# ElectroII_UPDATE.net
KiCad netlist of a schematic drawn in EAGLE
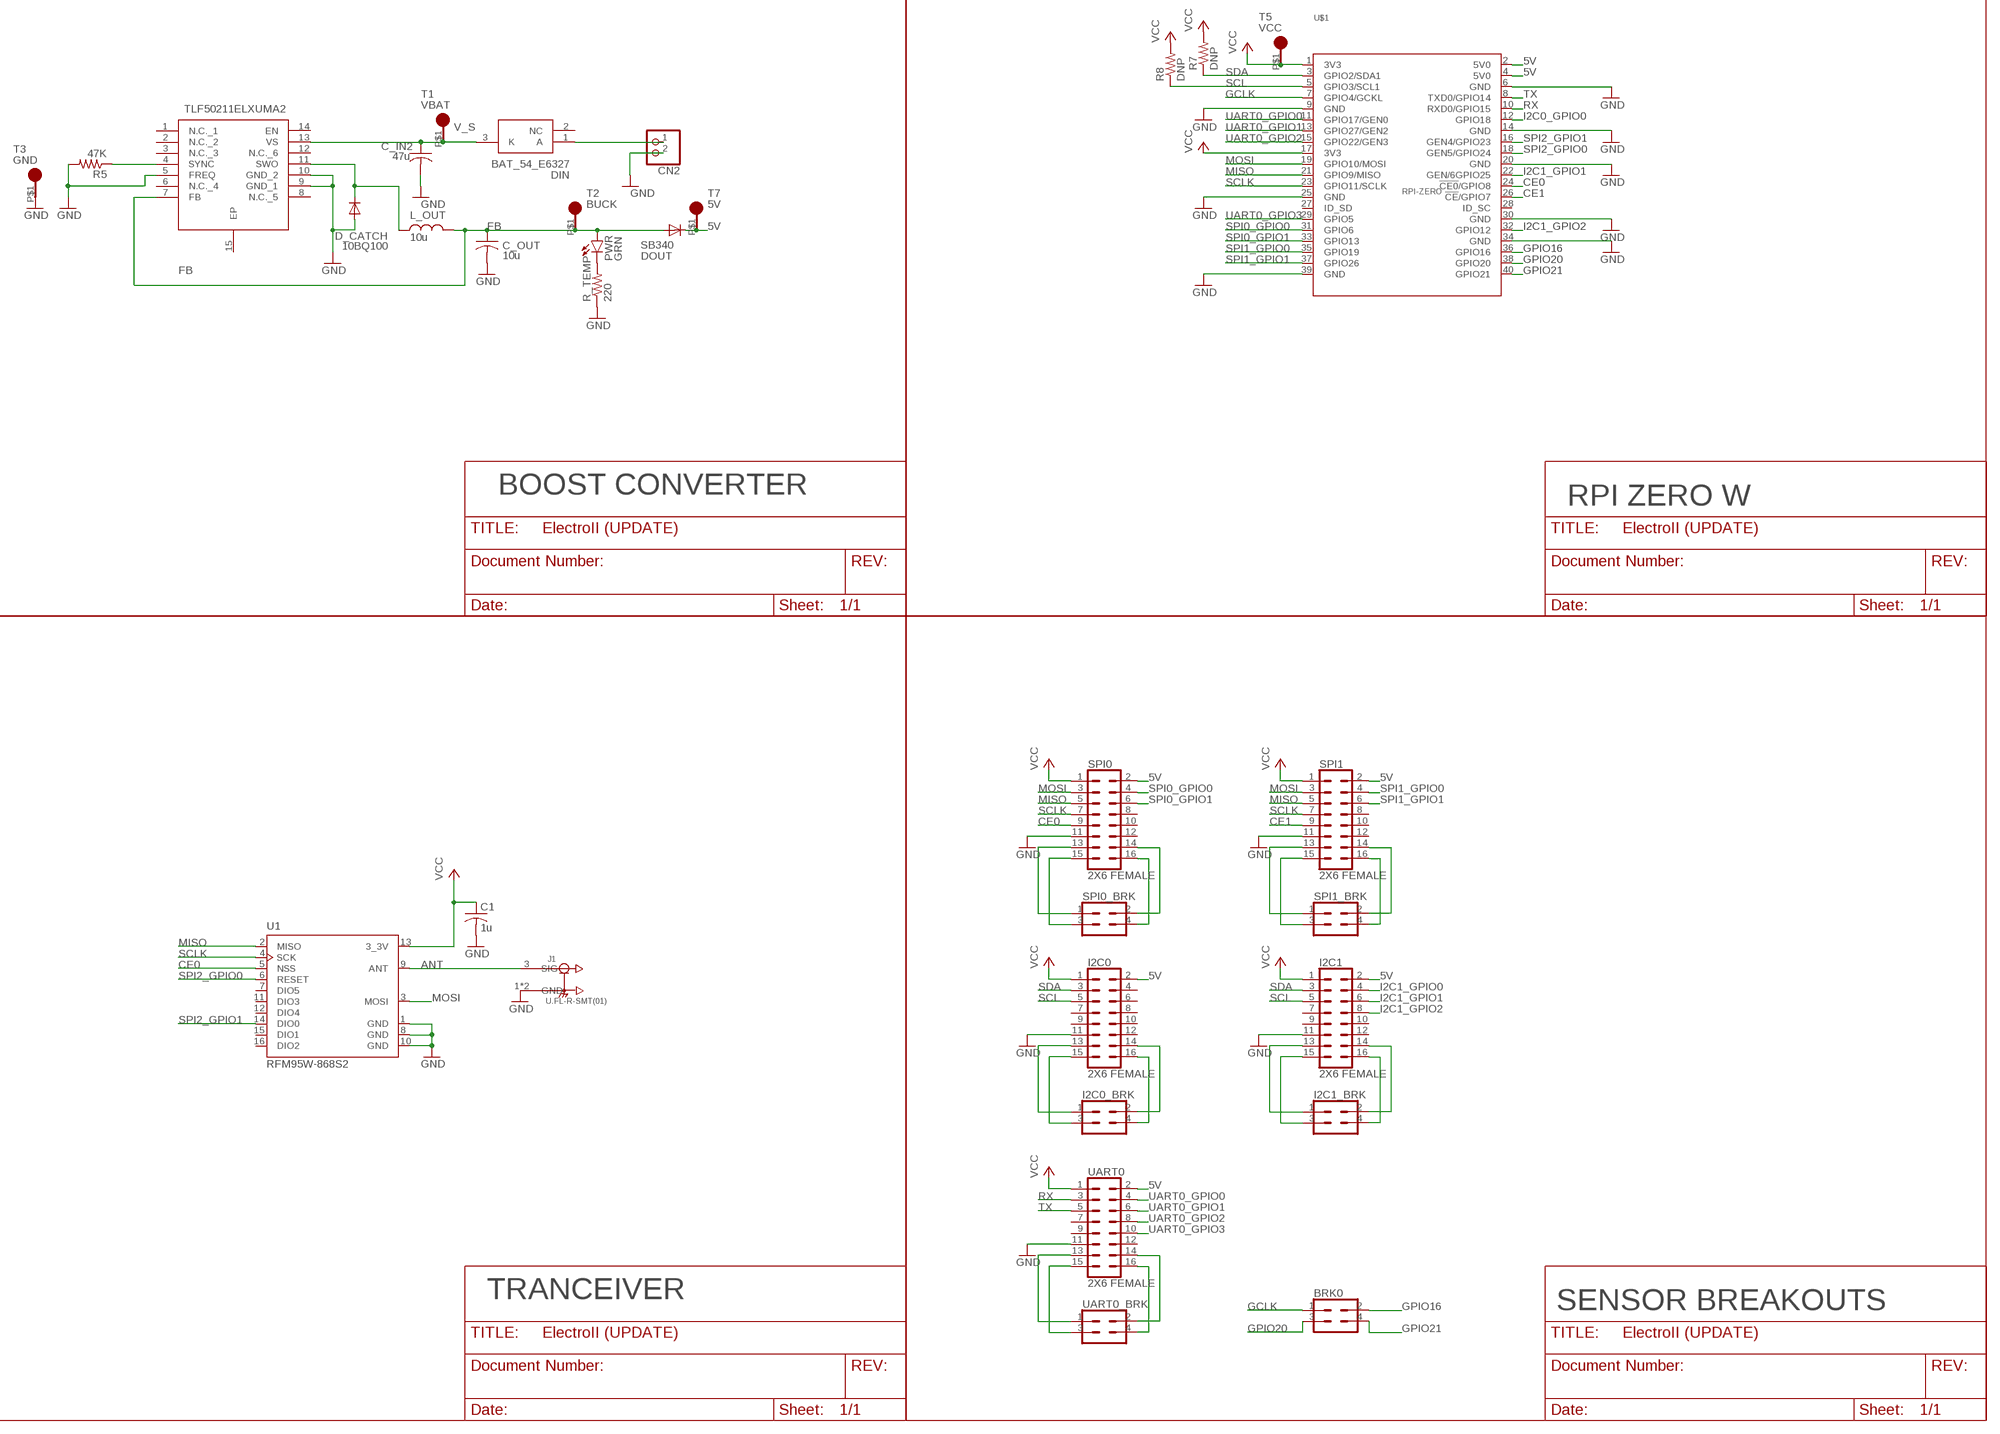
[diagram p0: schematic, sheet 1]

(export (version "E")
  (design (tool "Eeschema 10.0.6"))
  (components
    (comp (ref "BRK0")
      (value "SENSOR_PIN_BREAKOUT")
      (footprint "eagle-import:2X2")
      (libsource (lib "eagle-import") (part "SENSOR_PIN_BREAKOUT"))
    )
    (comp (ref "C1")
      (value "1u")
      (footprint "eagle-import:C1206")
      (libsource (lib "eagle-import") (part "C-ALL_PACKAGESC1206"))
    )
    (comp (ref "CN2")
      (value "JST_2PIN-SMT-RA")
      (footprint "eagle-import:JST-PH-2-SMT-RA")
      (libsource (lib "eagle-import") (part "JST_2PIN-SMT-RA"))
    )
    (comp (ref "C_IN2")
      (value "47u")
      (footprint "eagle-import:C1206")
      (libsource (lib "eagle-import") (part "C-ALL_PACKAGESC1206"))
    )
    (comp (ref "C_OUT")
      (value "10u")
      (footprint "eagle-import:C1206")
      (libsource (lib "eagle-import") (part "C-ALL_PACKAGESC1206"))
    )
    (comp (ref "DIN")
      (value "BAT_54_E6327")
      (footprint "eagle-import:SOT95P240X110-3N")
      (fields
        (field (name "MANUFACTURER_PART_NUMBER") "BAT 54 E6327")
        (field (name "MOUSER_PART_NUMBER") "726-BAT54E6327")
      )
      (libsource (lib "eagle-import") (part "BAT_54_E6327"))
    )
    (comp (ref "DOUT")
      (value "SB340")
      (footprint "eagle-import:DO41-10")
      (libsource (lib "eagle-import") (part "1N4004"))
    )
    (comp (ref "D_CATCH")
      (value "10BQ100")
      (footprint "eagle-import:DO41-10")
      (libsource (lib "eagle-import") (part "1N4004"))
    )
    (comp (ref "I2C0")
      (value "2X6 FEMALE")
      (footprint "eagle-import:2X7")
      (libsource (lib "eagle-import") (part "SENSOR_BREAKOUTPTH_FEMALE"))
    )
    (comp (ref "I2C0_BRK")
      (value "SENSOR_PIN_BREAKOUT")
      (footprint "eagle-import:2X2")
      (libsource (lib "eagle-import") (part "SENSOR_PIN_BREAKOUT"))
    )
    (comp (ref "I2C1")
      (value "2X6 FEMALE")
      (footprint "eagle-import:2X7")
      (libsource (lib "eagle-import") (part "SENSOR_BREAKOUTPTH_FEMALE"))
    )
    (comp (ref "I2C1_BRK")
      (value "SENSOR_PIN_BREAKOUT")
      (footprint "eagle-import:2X2")
      (libsource (lib "eagle-import") (part "SENSOR_PIN_BREAKOUT"))
    )
    (comp (ref "IC1")
      (value "TLF50211ELXUMA2")
      (footprint "eagle-import:SOP65P600X170-15N")
      (fields (field (name "MOUSER_PART_NUMBER") "726-TLF50211ELXUMA2"))
      (libsource (lib "eagle-import") (part "TLF50211ELXUMA2"))
    )
    (comp (ref "J1")
      (value "U.FL-R-SMT(01)")
      (footprint "eagle-import:HRS_U.FL-R-SMT(01)")
      (fields
        (field (name "DIGI-KEY_PART_NUMBER") "H9161-ND")
        (field (name "MF") "Hirose")
        (field (name "MP") "U.FL-R-SMT_01_")
      )
      (libsource (lib "eagle-import") (part "U.FL-R-SMT(01)"))
    )
    (comp (ref "L_OUT")
      (value "10u")
      (footprint "eagle-import:L-DS75LC")
      (libsource (lib "eagle-import") (part "L_SMD"))
    )
    (comp (ref "PWR")
      (value "GRN")
      (footprint "eagle-import:LED5MM")
      (libsource (lib "eagle-import") (part "LED5MM"))
    )
    (comp (ref "R5")
      (value "47K")
      (footprint "eagle-import:R1206")
      (libsource (lib "eagle-import") (part "R-ALL_PACKAGESR1206"))
    )
    (comp (ref "R7")
      (value "DNP")
      (footprint "eagle-import:R1206")
      (libsource (lib "eagle-import") (part "R-ALL_PACKAGESR1206"))
    )
    (comp (ref "R8")
      (value "DNP")
      (footprint "eagle-import:R1206")
      (libsource (lib "eagle-import") (part "R-ALL_PACKAGESR1206"))
    )
    (comp (ref "R_TEMP")
      (value "220")
      (footprint "eagle-import:R1206")
      (libsource (lib "eagle-import") (part "R-ALL_PACKAGESR1206"))
    )
    (comp (ref "SPI0")
      (value "2X6 FEMALE")
      (footprint "eagle-import:2X7")
      (libsource (lib "eagle-import") (part "SENSOR_BREAKOUTPTH_FEMALE"))
    )
    (comp (ref "SPI0_BRK")
      (value "SENSOR_PIN_BREAKOUT")
      (footprint "eagle-import:2X2")
      (libsource (lib "eagle-import") (part "SENSOR_PIN_BREAKOUT"))
    )
    (comp (ref "SPI1")
      (value "2X6 FEMALE")
      (footprint "eagle-import:2X7")
      (libsource (lib "eagle-import") (part "SENSOR_BREAKOUTPTH_FEMALE"))
    )
    (comp (ref "SPI1_BRK")
      (value "SENSOR_PIN_BREAKOUT")
      (footprint "eagle-import:2X2")
      (libsource (lib "eagle-import") (part "SENSOR_PIN_BREAKOUT"))
    )
    (comp (ref "T1")
      (value "VBAT")
      (footprint "eagle-import:TEST_PAD")
      (libsource (lib "eagle-import") (part "TEST_PAD"))
    )
    (comp (ref "T2")
      (value "BUCK")
      (footprint "eagle-import:TEST_PAD")
      (libsource (lib "eagle-import") (part "TEST_PAD"))
    )
    (comp (ref "T3")
      (value "GND")
      (footprint "eagle-import:TEST_PAD")
      (libsource (lib "eagle-import") (part "TEST_PAD"))
    )
    (comp (ref "T5")
      (value "VCC")
      (footprint "eagle-import:TEST_PAD")
      (libsource (lib "eagle-import") (part "TEST_PAD"))
    )
    (comp (ref "T7")
      (value "5V")
      (footprint "eagle-import:TEST_PAD")
      (libsource (lib "eagle-import") (part "TEST_PAD"))
    )
    (comp (ref "U$1")
      (value "RPI-ZERO")
      (footprint "eagle-import:RASP_PI_ZERO_BOARD_FULL")
      (libsource (lib "eagle-import") (part "RPI-ZERO"))
    )
    (comp (ref "U1")
      (value "RFM95W-868S2")
      (footprint "eagle-import:XCVR_RFM95W-868S2")
      (fields (field (name "MF") "RF"))
      (libsource (lib "eagle-import") (part "RFM95W-868S2"))
    )
    (comp (ref "UART0")
      (value "2X6 FEMALE")
      (footprint "eagle-import:2X7")
      (libsource (lib "eagle-import") (part "SENSOR_BREAKOUTPTH_FEMALE"))
    )
    (comp (ref "UART0_BRK")
      (value "SENSOR_PIN_BREAKOUT")
      (footprint "eagle-import:2X2")
      (libsource (lib "eagle-import") (part "SENSOR_PIN_BREAKOUT"))
    )
  )
  (nets
    (net (code "1") (name "/5V") (class "Default")
      (node (ref "DOUT") (pin "C") (pinfunction "C_C") (pintype "passive"))
      (node (ref "I2C0") (pin "2") (pinfunction "2_2") (pintype "passive"))
      (node (ref "I2C1") (pin "2") (pinfunction "2_2") (pintype "passive"))
      (node (ref "SPI0") (pin "2") (pinfunction "2_2") (pintype "passive"))
      (node (ref "SPI1") (pin "2") (pinfunction "2_2") (pintype "passive"))
      (node (ref "T7") (pin "P$1") (pinfunction "P$1_P$1") (pintype "passive"))
      (node (ref "U$1") (pin "2") (pinfunction "5V0_2") (pintype "power_in"))
      (node (ref "U$1") (pin "4") (pinfunction "5V0_4") (pintype "power_in"))
      (node (ref "UART0") (pin "2") (pinfunction "2_2") (pintype "passive"))
    )
    (net (code "2") (name "/ANT") (class "Default")
      (node (ref "J1") (pin "3") (pinfunction "SIG_3") (pintype "passive"))
      (node (ref "U1") (pin "9") (pinfunction "ANT_9") (pintype "passive"))
    )
    (net (code "3") (name "/CE0") (class "Default")
      (node (ref "SPI0") (pin "9") (pinfunction "9_9") (pintype "passive"))
      (node (ref "U$1") (pin "24") (pinfunction "~{CE0}/GPIO8_24") (pintype "bidirectional"))
      (node (ref "U1") (pin "5") (pinfunction "NSS_5") (pintype "input"))
    )
    (net (code "4") (name "/CE1") (class "Default")
      (node (ref "SPI1") (pin "9") (pinfunction "9_9") (pintype "passive"))
      (node (ref "U$1") (pin "26") (pinfunction "~{CE}/GPIO7_26") (pintype "bidirectional"))
    )
    (net (code "5") (name "/FB") (class "Default")
      (node (ref "C_OUT") (pin "1") (pinfunction "1_1") (pintype "passive"))
      (node (ref "DOUT") (pin "A") (pinfunction "A_A") (pintype "passive"))
      (node (ref "IC1") (pin "7") (pinfunction "FB_7") (pintype "bidirectional"))
      (node (ref "L_OUT") (pin "P$2") (pinfunction "2_P$2") (pintype "passive"))
      (node (ref "PWR") (pin "A") (pinfunction "A_A") (pintype "passive"))
      (node (ref "T2") (pin "P$1") (pinfunction "P$1_P$1") (pintype "passive"))
    )
    (net (code "6") (name "/GCLK") (class "Default")
      (node (ref "BRK0") (pin "1") (pinfunction "1_1") (pintype "passive"))
      (node (ref "U$1") (pin "7") (pinfunction "GPIO4/GCKL_7") (pintype "bidirectional"))
    )
    (net (code "7") (name "/GPIO16") (class "Default")
      (node (ref "BRK0") (pin "2") (pinfunction "2_2") (pintype "passive"))
      (node (ref "U$1") (pin "36") (pinfunction "GPIO16_36") (pintype "bidirectional"))
    )
    (net (code "8") (name "/GPIO20") (class "Default")
      (node (ref "BRK0") (pin "3") (pinfunction "3_3") (pintype "passive"))
      (node (ref "U$1") (pin "38") (pinfunction "GPIO20_38") (pintype "bidirectional"))
    )
    (net (code "9") (name "/GPIO21") (class "Default")
      (node (ref "BRK0") (pin "4") (pinfunction "4_4") (pintype "passive"))
      (node (ref "U$1") (pin "40") (pinfunction "GPIO21_40") (pintype "bidirectional"))
    )
    (net (code "10") (name "/I2C0_GPIO0") (class "Default")
      (node (ref "U$1") (pin "12") (pinfunction "GPIO18_12") (pintype "bidirectional"))
    )
    (net (code "11") (name "/I2C1_GPIO0") (class "Default")
      (node (ref "I2C1") (pin "4") (pinfunction "4_4") (pintype "passive"))
    )
    (net (code "12") (name "/I2C1_GPIO1") (class "Default")
      (node (ref "I2C1") (pin "6") (pinfunction "6_6") (pintype "passive"))
      (node (ref "U$1") (pin "22") (pinfunction "GEN/6GPIO25_22") (pintype "bidirectional"))
    )
    (net (code "13") (name "/I2C1_GPIO2") (class "Default")
      (node (ref "I2C1") (pin "8") (pinfunction "8_8") (pintype "passive"))
      (node (ref "U$1") (pin "32") (pinfunction "GPIO12_32") (pintype "bidirectional"))
    )
    (net (code "14") (name "/MISO") (class "Default")
      (node (ref "SPI0") (pin "5") (pinfunction "5_5") (pintype "passive"))
      (node (ref "SPI1") (pin "5") (pinfunction "5_5") (pintype "passive"))
      (node (ref "U$1") (pin "21") (pinfunction "GPIO9/MISO_21") (pintype "bidirectional"))
      (node (ref "U1") (pin "2") (pinfunction "MISO_2") (pintype "input"))
    )
    (net (code "15") (name "/MOSI") (class "Default")
      (node (ref "SPI0") (pin "3") (pinfunction "3_3") (pintype "passive"))
      (node (ref "SPI1") (pin "3") (pinfunction "3_3") (pintype "passive"))
      (node (ref "U$1") (pin "19") (pinfunction "GPIO10/MOSI_19") (pintype "bidirectional"))
      (node (ref "U1") (pin "3") (pinfunction "MOSI_3") (pintype "output"))
    )
    (net (code "16") (name "/RX") (class "Default")
      (node (ref "U$1") (pin "10") (pinfunction "RXD0/GPIO15_10") (pintype "bidirectional"))
      (node (ref "UART0") (pin "3") (pinfunction "3_3") (pintype "passive"))
    )
    (net (code "17") (name "/SCL") (class "Default")
      (node (ref "I2C0") (pin "5") (pinfunction "5_5") (pintype "passive"))
      (node (ref "I2C1") (pin "5") (pinfunction "5_5") (pintype "passive"))
      (node (ref "R8") (pin "1") (pinfunction "1_1") (pintype "passive"))
      (node (ref "U$1") (pin "5") (pinfunction "GPIO3/SCL1_5") (pintype "bidirectional"))
    )
    (net (code "18") (name "/SCLK") (class "Default")
      (node (ref "SPI0") (pin "7") (pinfunction "7_7") (pintype "passive"))
      (node (ref "SPI1") (pin "7") (pinfunction "7_7") (pintype "passive"))
      (node (ref "U$1") (pin "23") (pinfunction "GPIO11/SCLK_23") (pintype "bidirectional"))
      (node (ref "U1") (pin "4") (pinfunction "SCK_4") (pintype "input"))
    )
    (net (code "19") (name "/SDA") (class "Default")
      (node (ref "I2C0") (pin "3") (pinfunction "3_3") (pintype "passive"))
      (node (ref "I2C1") (pin "3") (pinfunction "3_3") (pintype "passive"))
      (node (ref "R7") (pin "1") (pinfunction "1_1") (pintype "passive"))
      (node (ref "U$1") (pin "3") (pinfunction "GPIO2/SDA1_3") (pintype "bidirectional"))
    )
    (net (code "20") (name "/SPI0_GPIO0") (class "Default")
      (node (ref "SPI0") (pin "4") (pinfunction "4_4") (pintype "passive"))
      (node (ref "U$1") (pin "31") (pinfunction "GPIO6_31") (pintype "bidirectional"))
    )
    (net (code "21") (name "/SPI0_GPIO1") (class "Default")
      (node (ref "SPI0") (pin "6") (pinfunction "6_6") (pintype "passive"))
      (node (ref "U$1") (pin "33") (pinfunction "GPIO13_33") (pintype "bidirectional"))
    )
    (net (code "22") (name "/SPI1_GPIO0") (class "Default")
      (node (ref "SPI1") (pin "4") (pinfunction "4_4") (pintype "passive"))
      (node (ref "U$1") (pin "35") (pinfunction "GPIO19_35") (pintype "bidirectional"))
    )
    (net (code "23") (name "/SPI1_GPIO1") (class "Default")
      (node (ref "SPI1") (pin "6") (pinfunction "6_6") (pintype "passive"))
      (node (ref "U$1") (pin "37") (pinfunction "GPIO26_37") (pintype "bidirectional"))
    )
    (net (code "24") (name "/SPI2_GPIO0") (class "Default")
      (node (ref "U$1") (pin "18") (pinfunction "GEN5/GPIO24_18") (pintype "bidirectional"))
      (node (ref "U1") (pin "6") (pinfunction "RESET_6") (pintype "bidirectional"))
    )
    (net (code "25") (name "/SPI2_GPIO1") (class "Default")
      (node (ref "U$1") (pin "16") (pinfunction "GEN4/GPIO23_16") (pintype "bidirectional"))
      (node (ref "U1") (pin "14") (pinfunction "DIO0_14") (pintype "bidirectional"))
    )
    (net (code "26") (name "/TX") (class "Default")
      (node (ref "U$1") (pin "8") (pinfunction "TXD0/GPIO14_8") (pintype "bidirectional"))
      (node (ref "UART0") (pin "5") (pinfunction "5_5") (pintype "passive"))
    )
    (net (code "27") (name "/UART0_GPIO0") (class "Default")
      (node (ref "U$1") (pin "11") (pinfunction "GPIO17/GEN0_11") (pintype "bidirectional"))
      (node (ref "UART0") (pin "4") (pinfunction "4_4") (pintype "passive"))
    )
    (net (code "28") (name "/UART0_GPIO1") (class "Default")
      (node (ref "U$1") (pin "13") (pinfunction "GPIO27/GEN2_13") (pintype "bidirectional"))
      (node (ref "UART0") (pin "6") (pinfunction "6_6") (pintype "passive"))
    )
    (net (code "29") (name "/UART0_GPIO2") (class "Default")
      (node (ref "U$1") (pin "15") (pinfunction "GPIO22/GEN3_15") (pintype "bidirectional"))
      (node (ref "UART0") (pin "8") (pinfunction "8_8") (pintype "passive"))
    )
    (net (code "30") (name "/UART0_GPIO3") (class "Default")
      (node (ref "U$1") (pin "29") (pinfunction "GPIO5_29") (pintype "bidirectional"))
      (node (ref "UART0") (pin "10") (pinfunction "10_10") (pintype "passive"))
    )
    (net (code "31") (name "/V_S") (class "Default")
      (node (ref "C_IN2") (pin "1") (pinfunction "1_1") (pintype "passive"))
      (node (ref "DIN") (pin "3") (pinfunction "K_3") (pintype "bidirectional"))
      (node (ref "IC1") (pin "13") (pinfunction "VS_13") (pintype "bidirectional"))
      (node (ref "T1") (pin "P$1") (pinfunction "P$1_P$1") (pintype "passive"))
    )
    (net (code "32") (name "GND") (class "Default")
      (node (ref "C1") (pin "2") (pinfunction "2_2") (pintype "passive"))
      (node (ref "CN2") (pin "2") (pinfunction "1_2") (pintype "passive"))
      (node (ref "C_IN2") (pin "2") (pinfunction "2_2") (pintype "passive"))
      (node (ref "C_OUT") (pin "2") (pinfunction "2_2") (pintype "passive"))
      (node (ref "D_CATCH") (pin "A") (pinfunction "A_A") (pintype "passive"))
      (node (ref "I2C0") (pin "11") (pinfunction "11_11") (pintype "passive"))
      (node (ref "I2C1") (pin "11") (pinfunction "11_11") (pintype "passive"))
      (node (ref "IC1") (pin "10") (pinfunction "GND_2_10") (pintype "bidirectional"))
      (node (ref "IC1") (pin "5") (pinfunction "FREQ_5") (pintype "bidirectional"))
      (node (ref "IC1") (pin "9") (pinfunction "GND_1_9") (pintype "bidirectional"))
      (node (ref "J1") (pin "1") (pinfunction "GND_1") (pintype "passive"))
      (node (ref "J1") (pin "2") (pinfunction "GND_2") (pintype "passive"))
      (node (ref "R5") (pin "2") (pinfunction "2_2") (pintype "passive"))
      (node (ref "R_TEMP") (pin "1") (pinfunction "1_1") (pintype "passive"))
      (node (ref "SPI0") (pin "11") (pinfunction "11_11") (pintype "passive"))
      (node (ref "SPI1") (pin "11") (pinfunction "11_11") (pintype "passive"))
      (node (ref "T3") (pin "P$1") (pinfunction "P$1_P$1") (pintype "passive"))
      (node (ref "U$1") (pin "14") (pinfunction "GND_14") (pintype "power_in"))
      (node (ref "U$1") (pin "20") (pinfunction "GND_20") (pintype "power_in"))
      (node (ref "U$1") (pin "25") (pinfunction "GND_25") (pintype "power_in"))
      (node (ref "U$1") (pin "30") (pinfunction "GND_30") (pintype "power_in"))
      (node (ref "U$1") (pin "34") (pinfunction "GND_34") (pintype "power_in"))
      (node (ref "U$1") (pin "39") (pinfunction "GND_39") (pintype "power_in"))
      (node (ref "U$1") (pin "6") (pinfunction "GND_6") (pintype "power_in"))
      (node (ref "U$1") (pin "9") (pinfunction "GND_9") (pintype "power_in"))
      (node (ref "U1") (pin "1") (pinfunction "GND_1") (pintype "power_in"))
      (node (ref "U1") (pin "10") (pinfunction "GND_10") (pintype "power_in"))
      (node (ref "U1") (pin "8") (pinfunction "GND_8") (pintype "power_in"))
      (node (ref "UART0") (pin "11") (pinfunction "11_11") (pintype "passive"))
    )
    (net (code "33") (name "Net-(CN2-2)") (class "Default")
      (node (ref "CN2") (pin "1") (pinfunction "2_1") (pintype "passive"))
      (node (ref "DIN") (pin "1") (pinfunction "A_1") (pintype "bidirectional"))
    )
    (net (code "34") (name "Net-(I2C0-Pad13)") (class "Default")
      (node (ref "I2C0") (pin "13") (pinfunction "13_13") (pintype "passive"))
      (node (ref "I2C0_BRK") (pin "1") (pinfunction "1_1") (pintype "passive"))
    )
    (net (code "35") (name "Net-(I2C0-Pad14)") (class "Default")
      (node (ref "I2C0") (pin "14") (pinfunction "14_14") (pintype "passive"))
      (node (ref "I2C0_BRK") (pin "2") (pinfunction "2_2") (pintype "passive"))
    )
    (net (code "36") (name "Net-(I2C0-Pad15)") (class "Default")
      (node (ref "I2C0") (pin "15") (pinfunction "15_15") (pintype "passive"))
      (node (ref "I2C0_BRK") (pin "3") (pinfunction "3_3") (pintype "passive"))
    )
    (net (code "37") (name "Net-(I2C0-Pad16)") (class "Default")
      (node (ref "I2C0") (pin "16") (pinfunction "16_16") (pintype "passive"))
      (node (ref "I2C0_BRK") (pin "4") (pinfunction "4_4") (pintype "passive"))
    )
    (net (code "38") (name "Net-(I2C1-Pad13)") (class "Default")
      (node (ref "I2C1") (pin "13") (pinfunction "13_13") (pintype "passive"))
      (node (ref "I2C1_BRK") (pin "1") (pinfunction "1_1") (pintype "passive"))
    )
    (net (code "39") (name "Net-(I2C1-Pad14)") (class "Default")
      (node (ref "I2C1") (pin "14") (pinfunction "14_14") (pintype "passive"))
      (node (ref "I2C1_BRK") (pin "2") (pinfunction "2_2") (pintype "passive"))
    )
    (net (code "40") (name "Net-(I2C1-Pad15)") (class "Default")
      (node (ref "I2C1") (pin "15") (pinfunction "15_15") (pintype "passive"))
      (node (ref "I2C1_BRK") (pin "3") (pinfunction "3_3") (pintype "passive"))
    )
    (net (code "41") (name "Net-(I2C1-Pad16)") (class "Default")
      (node (ref "I2C1") (pin "16") (pinfunction "16_16") (pintype "passive"))
      (node (ref "I2C1_BRK") (pin "4") (pinfunction "4_4") (pintype "passive"))
    )
    (net (code "42") (name "Net-(IC1-SWO)") (class "Default")
      (node (ref "D_CATCH") (pin "C") (pinfunction "C_C") (pintype "passive"))
      (node (ref "IC1") (pin "11") (pinfunction "SWO_11") (pintype "bidirectional"))
      (node (ref "L_OUT") (pin "P$1") (pinfunction "1_P$1") (pintype "passive"))
    )
    (net (code "43") (name "Net-(IC1-SYNC)") (class "Default")
      (node (ref "IC1") (pin "4") (pinfunction "SYNC_4") (pintype "bidirectional"))
      (node (ref "R5") (pin "1") (pinfunction "1_1") (pintype "passive"))
    )
    (net (code "44") (name "Net-(PWR-C)") (class "Default")
      (node (ref "PWR") (pin "K") (pinfunction "C_K") (pintype "passive"))
      (node (ref "R_TEMP") (pin "2") (pinfunction "2_2") (pintype "passive"))
    )
    (net (code "45") (name "Net-(SPI0-Pad13)") (class "Default")
      (node (ref "SPI0") (pin "13") (pinfunction "13_13") (pintype "passive"))
      (node (ref "SPI0_BRK") (pin "1") (pinfunction "1_1") (pintype "passive"))
    )
    (net (code "46") (name "Net-(SPI0-Pad14)") (class "Default")
      (node (ref "SPI0") (pin "14") (pinfunction "14_14") (pintype "passive"))
      (node (ref "SPI0_BRK") (pin "2") (pinfunction "2_2") (pintype "passive"))
    )
    (net (code "47") (name "Net-(SPI0-Pad15)") (class "Default")
      (node (ref "SPI0") (pin "15") (pinfunction "15_15") (pintype "passive"))
      (node (ref "SPI0_BRK") (pin "3") (pinfunction "3_3") (pintype "passive"))
    )
    (net (code "48") (name "Net-(SPI0-Pad16)") (class "Default")
      (node (ref "SPI0") (pin "16") (pinfunction "16_16") (pintype "passive"))
      (node (ref "SPI0_BRK") (pin "4") (pinfunction "4_4") (pintype "passive"))
    )
    (net (code "49") (name "Net-(SPI1-Pad13)") (class "Default")
      (node (ref "SPI1") (pin "13") (pinfunction "13_13") (pintype "passive"))
      (node (ref "SPI1_BRK") (pin "1") (pinfunction "1_1") (pintype "passive"))
    )
    (net (code "50") (name "Net-(SPI1-Pad14)") (class "Default")
      (node (ref "SPI1") (pin "14") (pinfunction "14_14") (pintype "passive"))
      (node (ref "SPI1_BRK") (pin "2") (pinfunction "2_2") (pintype "passive"))
    )
    (net (code "51") (name "Net-(SPI1-Pad15)") (class "Default")
      (node (ref "SPI1") (pin "15") (pinfunction "15_15") (pintype "passive"))
      (node (ref "SPI1_BRK") (pin "3") (pinfunction "3_3") (pintype "passive"))
    )
    (net (code "52") (name "Net-(SPI1-Pad16)") (class "Default")
      (node (ref "SPI1") (pin "16") (pinfunction "16_16") (pintype "passive"))
      (node (ref "SPI1_BRK") (pin "4") (pinfunction "4_4") (pintype "passive"))
    )
    (net (code "53") (name "Net-(UART0-Pad13)") (class "Default")
      (node (ref "UART0") (pin "13") (pinfunction "13_13") (pintype "passive"))
      (node (ref "UART0_BRK") (pin "1") (pinfunction "1_1") (pintype "passive"))
    )
    (net (code "54") (name "Net-(UART0-Pad14)") (class "Default")
      (node (ref "UART0") (pin "14") (pinfunction "14_14") (pintype "passive"))
      (node (ref "UART0_BRK") (pin "2") (pinfunction "2_2") (pintype "passive"))
    )
    (net (code "55") (name "Net-(UART0-Pad15)") (class "Default")
      (node (ref "UART0") (pin "15") (pinfunction "15_15") (pintype "passive"))
      (node (ref "UART0_BRK") (pin "3") (pinfunction "3_3") (pintype "passive"))
    )
    (net (code "56") (name "Net-(UART0-Pad16)") (class "Default")
      (node (ref "UART0") (pin "16") (pinfunction "16_16") (pintype "passive"))
      (node (ref "UART0_BRK") (pin "4") (pinfunction "4_4") (pintype "passive"))
    )
    (net (code "57") (name "VCC") (class "Default")
      (node (ref "C1") (pin "1") (pinfunction "1_1") (pintype "passive"))
      (node (ref "I2C0") (pin "1") (pinfunction "1_1") (pintype "passive"))
      (node (ref "I2C1") (pin "1") (pinfunction "1_1") (pintype "passive"))
      (node (ref "R7") (pin "2") (pinfunction "2_2") (pintype "passive"))
      (node (ref "R8") (pin "2") (pinfunction "2_2") (pintype "passive"))
      (node (ref "SPI0") (pin "1") (pinfunction "1_1") (pintype "passive"))
      (node (ref "SPI1") (pin "1") (pinfunction "1_1") (pintype "passive"))
      (node (ref "T5") (pin "P$1") (pinfunction "P$1_P$1") (pintype "passive"))
      (node (ref "U$1") (pin "1") (pinfunction "3V3_1") (pintype "power_in"))
      (node (ref "U$1") (pin "17") (pinfunction "3V3_17") (pintype "power_in"))
      (node (ref "U1") (pin "13") (pinfunction "3_3V_13") (pintype "power_in"))
      (node (ref "UART0") (pin "1") (pinfunction "1_1") (pintype "passive"))
    )
    (net (code "58") (name "unconnected-(DIN-NC-Pad2)") (class "Default")
      (node (ref "DIN") (pin "2") (pinfunction "NC_2") (pintype "no_connect"))
    )
    (net (code "59") (name "unconnected-(I2C0-Pad4)") (class "Default")
      (node (ref "I2C0") (pin "4") (pinfunction "4_4") (pintype "passive"))
    )
    (net (code "60") (name "unconnected-(I2C0-Pad6)") (class "Default")
      (node (ref "I2C0") (pin "6") (pinfunction "6_6") (pintype "passive"))
    )
    (net (code "61") (name "unconnected-(I2C0-Pad7)") (class "Default")
      (node (ref "I2C0") (pin "7") (pinfunction "7_7") (pintype "passive"))
    )
    (net (code "62") (name "unconnected-(I2C0-Pad8)") (class "Default")
      (node (ref "I2C0") (pin "8") (pinfunction "8_8") (pintype "passive"))
    )
    (net (code "63") (name "unconnected-(I2C0-Pad9)") (class "Default")
      (node (ref "I2C0") (pin "9") (pinfunction "9_9") (pintype "passive"))
    )
    (net (code "64") (name "unconnected-(I2C0-Pad10)") (class "Default")
      (node (ref "I2C0") (pin "10") (pinfunction "10_10") (pintype "passive"))
    )
    (net (code "65") (name "unconnected-(I2C0-Pad12)") (class "Default")
      (node (ref "I2C0") (pin "12") (pinfunction "12_12") (pintype "passive"))
    )
    (net (code "66") (name "unconnected-(I2C1-Pad7)") (class "Default")
      (node (ref "I2C1") (pin "7") (pinfunction "7_7") (pintype "passive"))
    )
    (net (code "67") (name "unconnected-(I2C1-Pad9)") (class "Default")
      (node (ref "I2C1") (pin "9") (pinfunction "9_9") (pintype "passive"))
    )
    (net (code "68") (name "unconnected-(I2C1-Pad10)") (class "Default")
      (node (ref "I2C1") (pin "10") (pinfunction "10_10") (pintype "passive"))
    )
    (net (code "69") (name "unconnected-(I2C1-Pad12)") (class "Default")
      (node (ref "I2C1") (pin "12") (pinfunction "12_12") (pintype "passive"))
    )
    (net (code "70") (name "unconnected-(IC1-EN-Pad14)") (class "Default")
      (node (ref "IC1") (pin "14") (pinfunction "EN_14") (pintype "bidirectional"))
    )
    (net (code "71") (name "unconnected-(IC1-EP-Pad15)") (class "Default")
      (node (ref "IC1") (pin "15") (pinfunction "EP_15") (pintype "bidirectional"))
    )
    (net (code "72") (name "unconnected-(IC1-N.C._1-Pad1)") (class "Default")
      (node (ref "IC1") (pin "1") (pinfunction "N.C._1_1") (pintype "bidirectional"))
    )
    (net (code "73") (name "unconnected-(IC1-N.C._2-Pad2)") (class "Default")
      (node (ref "IC1") (pin "2") (pinfunction "N.C._2_2") (pintype "bidirectional"))
    )
    (net (code "74") (name "unconnected-(IC1-N.C._3-Pad3)") (class "Default")
      (node (ref "IC1") (pin "3") (pinfunction "N.C._3_3") (pintype "bidirectional"))
    )
    (net (code "75") (name "unconnected-(IC1-N.C._4-Pad6)") (class "Default")
      (node (ref "IC1") (pin "6") (pinfunction "N.C._4_6") (pintype "bidirectional"))
    )
    (net (code "76") (name "unconnected-(IC1-N.C._5-Pad8)") (class "Default")
      (node (ref "IC1") (pin "8") (pinfunction "N.C._5_8") (pintype "bidirectional"))
    )
    (net (code "77") (name "unconnected-(IC1-N.C._6-Pad12)") (class "Default")
      (node (ref "IC1") (pin "12") (pinfunction "N.C._6_12") (pintype "bidirectional"))
    )
    (net (code "78") (name "unconnected-(SPI0-Pad8)") (class "Default")
      (node (ref "SPI0") (pin "8") (pinfunction "8_8") (pintype "passive"))
    )
    (net (code "79") (name "unconnected-(SPI0-Pad10)") (class "Default")
      (node (ref "SPI0") (pin "10") (pinfunction "10_10") (pintype "passive"))
    )
    (net (code "80") (name "unconnected-(SPI0-Pad12)") (class "Default")
      (node (ref "SPI0") (pin "12") (pinfunction "12_12") (pintype "passive"))
    )
    (net (code "81") (name "unconnected-(SPI1-Pad8)") (class "Default")
      (node (ref "SPI1") (pin "8") (pinfunction "8_8") (pintype "passive"))
    )
    (net (code "82") (name "unconnected-(SPI1-Pad10)") (class "Default")
      (node (ref "SPI1") (pin "10") (pinfunction "10_10") (pintype "passive"))
    )
    (net (code "83") (name "unconnected-(SPI1-Pad12)") (class "Default")
      (node (ref "SPI1") (pin "12") (pinfunction "12_12") (pintype "passive"))
    )
    (net (code "84") (name "unconnected-(U$1-ID_SC-Pad28)") (class "Default")
      (node (ref "U$1") (pin "28") (pinfunction "ID_SC_28") (pintype "bidirectional"))
    )
    (net (code "85") (name "unconnected-(U$1-ID_SD-Pad27)") (class "Default")
      (node (ref "U$1") (pin "27") (pinfunction "ID_SD_27") (pintype "bidirectional"))
    )
    (net (code "86") (name "unconnected-(U1-DIO1-Pad15)") (class "Default")
      (node (ref "U1") (pin "15") (pinfunction "DIO1_15") (pintype "bidirectional"))
    )
    (net (code "87") (name "unconnected-(U1-DIO2-Pad16)") (class "Default")
      (node (ref "U1") (pin "16") (pinfunction "DIO2_16") (pintype "bidirectional"))
    )
    (net (code "88") (name "unconnected-(U1-DIO3-Pad11)") (class "Default")
      (node (ref "U1") (pin "11") (pinfunction "DIO3_11") (pintype "bidirectional"))
    )
    (net (code "89") (name "unconnected-(U1-DIO4-Pad12)") (class "Default")
      (node (ref "U1") (pin "12") (pinfunction "DIO4_12") (pintype "bidirectional"))
    )
    (net (code "90") (name "unconnected-(U1-DIO5-Pad7)") (class "Default")
      (node (ref "U1") (pin "7") (pinfunction "DIO5_7") (pintype "bidirectional"))
    )
    (net (code "91") (name "unconnected-(UART0-Pad7)") (class "Default")
      (node (ref "UART0") (pin "7") (pinfunction "7_7") (pintype "passive"))
    )
    (net (code "92") (name "unconnected-(UART0-Pad9)") (class "Default")
      (node (ref "UART0") (pin "9") (pinfunction "9_9") (pintype "passive"))
    )
    (net (code "93") (name "unconnected-(UART0-Pad12)") (class "Default")
      (node (ref "UART0") (pin "12") (pinfunction "12_12") (pintype "passive"))
    )
  )
)
